# jackdemo.net
KiCad netlist of a schematic drawn in EAGLE
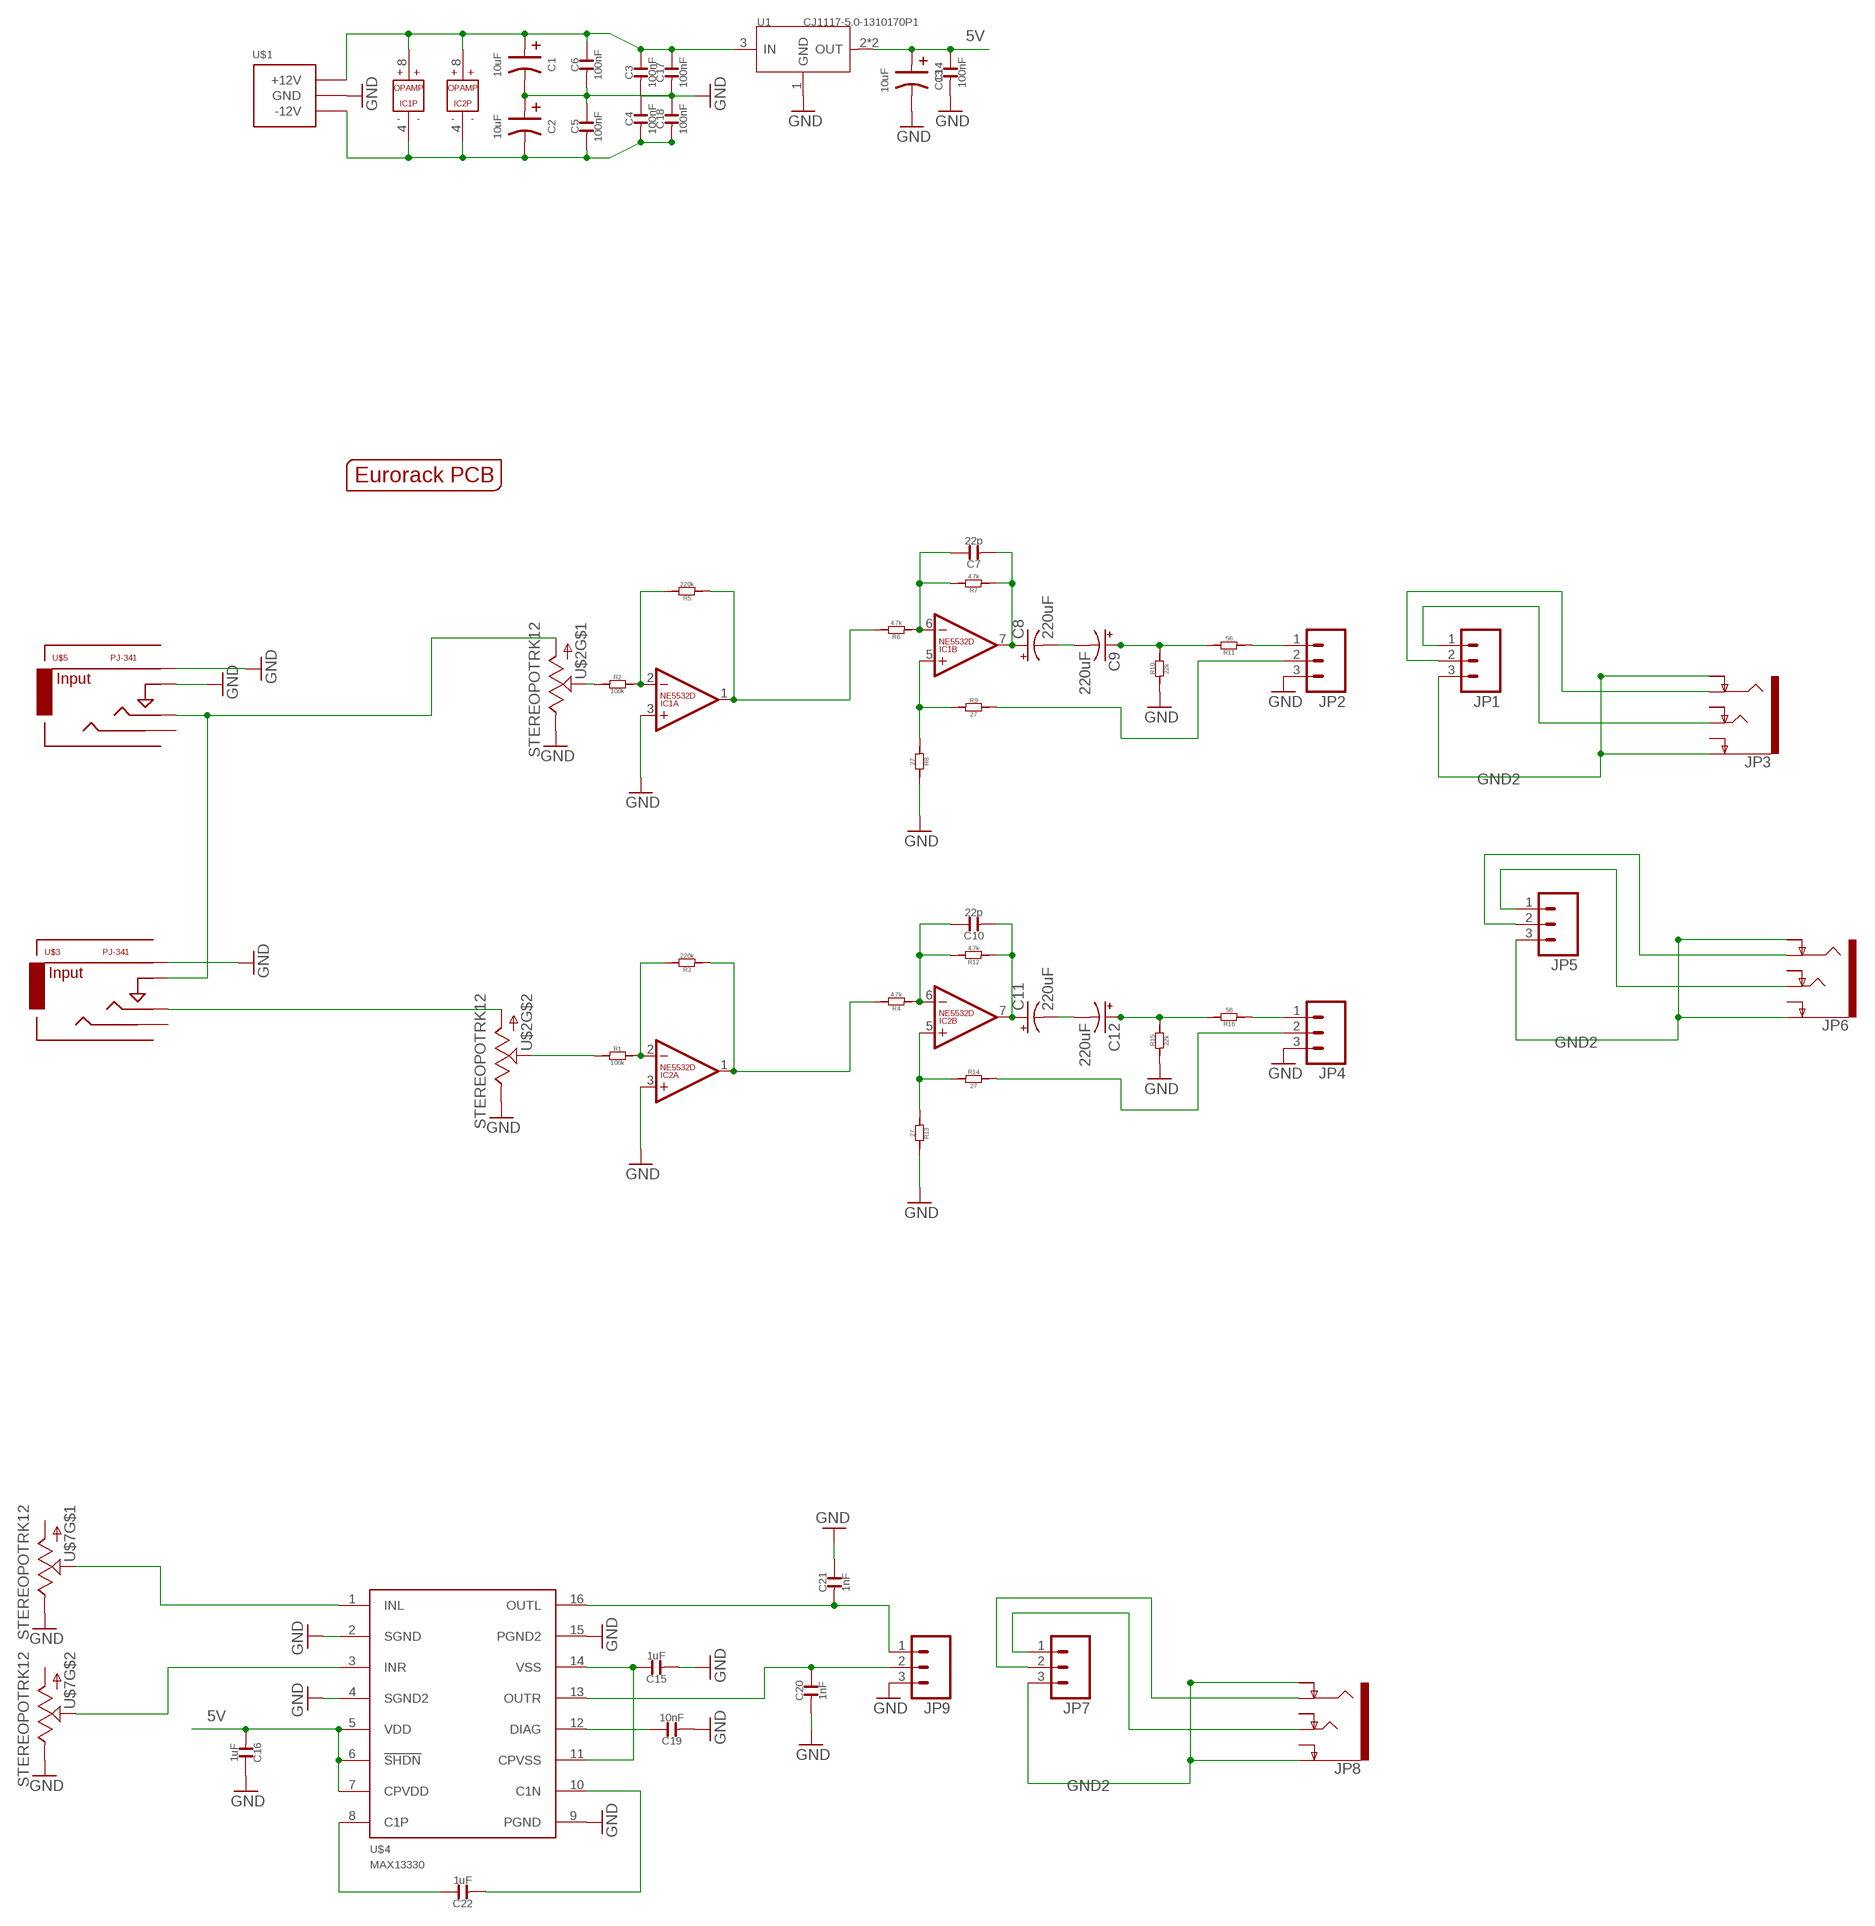
[diagram p0: schematic, sheet 1]

(export (version "E")
  (design (tool "Eeschema 10.0.6"))
  (components
    (comp (ref "C1")
      (value "10uF")
      (footprint "eagle-import:AVX-A")
      (libsource (lib "eagle-import") (part "C-POLAR-A"))
    )
    (comp (ref "C2")
      (value "10uF")
      (footprint "eagle-import:AVX-A")
      (libsource (lib "eagle-import") (part "C-POLAR-A"))
    )
    (comp (ref "C3")
      (value "100nF")
      (footprint "eagle-import:C0603")
      (libsource (lib "eagle-import") (part "C-0603"))
    )
    (comp (ref "C4")
      (value "100nF")
      (footprint "eagle-import:C0603")
      (libsource (lib "eagle-import") (part "C-0603"))
    )
    (comp (ref "C5")
      (value "100nF")
      (footprint "eagle-import:C0603")
      (libsource (lib "eagle-import") (part "C-0603"))
    )
    (comp (ref "C6")
      (value "100nF")
      (footprint "eagle-import:C0603")
      (libsource (lib "eagle-import") (part "C-0603"))
    )
    (comp (ref "C7")
      (value "22p")
      (footprint "eagle-import:C0603")
      (libsource (lib "eagle-import") (part "C-0603"))
    )
    (comp (ref "C8")
      (value "220uF")
      (footprint "eagle-import:153CLV-0505")
      (libsource (lib "eagle-import") (part "CPOL-US153CLV-0505"))
    )
    (comp (ref "C9")
      (value "220uF")
      (footprint "eagle-import:153CLV-0505")
      (libsource (lib "eagle-import") (part "CPOL-US153CLV-0505"))
    )
    (comp (ref "C10")
      (value "22p")
      (footprint "eagle-import:C0603")
      (libsource (lib "eagle-import") (part "C-0603"))
    )
    (comp (ref "C11")
      (value "220uF")
      (footprint "eagle-import:153CLV-0505")
      (libsource (lib "eagle-import") (part "CPOL-US153CLV-0505"))
    )
    (comp (ref "C12")
      (value "220uF")
      (footprint "eagle-import:153CLV-0505")
      (libsource (lib "eagle-import") (part "CPOL-US153CLV-0505"))
    )
    (comp (ref "C13")
      (value "10uF")
      (footprint "eagle-import:AVX-A")
      (libsource (lib "eagle-import") (part "C-POLAR-A"))
    )
    (comp (ref "C14")
      (value "100nF")
      (footprint "eagle-import:C0603")
      (libsource (lib "eagle-import") (part "C-0603"))
    )
    (comp (ref "C15")
      (value "1uF")
      (footprint "eagle-import:C0603")
      (libsource (lib "eagle-import") (part "C-0603"))
    )
    (comp (ref "C16")
      (value "1uF")
      (footprint "eagle-import:C0603")
      (libsource (lib "eagle-import") (part "C-0603"))
    )
    (comp (ref "C17")
      (value "100nF")
      (footprint "eagle-import:C0603")
      (libsource (lib "eagle-import") (part "C-0603"))
    )
    (comp (ref "C18")
      (value "100nF")
      (footprint "eagle-import:C0603")
      (libsource (lib "eagle-import") (part "C-0603"))
    )
    (comp (ref "C19")
      (value "10nF")
      (footprint "eagle-import:C0603")
      (libsource (lib "eagle-import") (part "C-0603"))
    )
    (comp (ref "C20")
      (value "1nF")
      (footprint "eagle-import:C0603")
      (libsource (lib "eagle-import") (part "C-0603"))
    )
    (comp (ref "C21")
      (value "1nF")
      (footprint "eagle-import:C0603")
      (libsource (lib "eagle-import") (part "C-0603"))
    )
    (comp (ref "C22")
      (value "1uF")
      (footprint "eagle-import:C0603")
      (libsource (lib "eagle-import") (part "C-0603"))
    )
    (comp (ref "IC1")
      (value "NE5532D")
      (footprint "eagle-import:SO08")
      (libsource (lib "eagle-import") (part "NE5532D"))
    )
    (comp (ref "IC2")
      (value "NE5532D")
      (footprint "eagle-import:SO08")
      (libsource (lib "eagle-import") (part "NE5532D"))
    )
    (comp (ref "JP1")
      (value "M03PTH")
      (footprint "eagle-import:1X03")
      (libsource (lib "eagle-import") (part "M03PTH"))
    )
    (comp (ref "JP2")
      (value "M03PTH")
      (footprint "eagle-import:1X03")
      (libsource (lib "eagle-import") (part "M03PTH"))
    )
    (comp (ref "JP3")
      (value "AUDIO-JACK4-.25-HORIZ-TRS")
      (footprint "eagle-import:AUDIO-JACK-.25-INCH-HORIZ-PTH")
      (libsource (lib "eagle-import") (part "AUDIO-JACK4-.25-HORIZ-TRS"))
    )
    (comp (ref "JP4")
      (value "M03PTH")
      (footprint "eagle-import:1X03")
      (libsource (lib "eagle-import") (part "M03PTH"))
    )
    (comp (ref "JP5")
      (value "M03PTH")
      (footprint "eagle-import:1X03")
      (libsource (lib "eagle-import") (part "M03PTH"))
    )
    (comp (ref "JP6")
      (value "AUDIO-JACK4-.25-HORIZ-TRS")
      (footprint "eagle-import:AUDIO-JACK-.25-INCH-HORIZ-PTH")
      (libsource (lib "eagle-import") (part "AUDIO-JACK4-.25-HORIZ-TRS"))
    )
    (comp (ref "JP7")
      (value "M03PTH")
      (footprint "eagle-import:1X03")
      (libsource (lib "eagle-import") (part "M03PTH"))
    )
    (comp (ref "JP8")
      (value "AUDIO-JACK4-.25-HORIZ-TRS")
      (footprint "eagle-import:AUDIO-JACK-.25-INCH-HORIZ-PTH")
      (libsource (lib "eagle-import") (part "AUDIO-JACK4-.25-HORIZ-TRS"))
    )
    (comp (ref "JP9")
      (value "M03PTH")
      (footprint "eagle-import:1X03")
      (libsource (lib "eagle-import") (part "M03PTH"))
    )
    (comp (ref "R1")
      (value "100k")
      (footprint "eagle-import:R0603")
      (libsource (lib "eagle-import") (part "R-0603"))
    )
    (comp (ref "R2")
      (value "100k")
      (footprint "eagle-import:R0603")
      (libsource (lib "eagle-import") (part "R-0603"))
    )
    (comp (ref "R3")
      (value "220k")
      (footprint "eagle-import:R0603")
      (libsource (lib "eagle-import") (part "R-0603"))
    )
    (comp (ref "R4")
      (value "4.7k")
      (footprint "eagle-import:R0603")
      (libsource (lib "eagle-import") (part "R-0603"))
    )
    (comp (ref "R5")
      (value "220k")
      (footprint "eagle-import:R0603")
      (libsource (lib "eagle-import") (part "R-0603"))
    )
    (comp (ref "R6")
      (value "4.7k")
      (footprint "eagle-import:R0603")
      (libsource (lib "eagle-import") (part "R-0603"))
    )
    (comp (ref "R7")
      (value "4.7k")
      (footprint "eagle-import:R0603")
      (libsource (lib "eagle-import") (part "R-0603"))
    )
    (comp (ref "R8")
      (value "27")
      (footprint "eagle-import:R0603")
      (libsource (lib "eagle-import") (part "R-0603"))
    )
    (comp (ref "R9")
      (value "27")
      (footprint "eagle-import:R0603")
      (libsource (lib "eagle-import") (part "R-0603"))
    )
    (comp (ref "R10")
      (value "22k")
      (footprint "eagle-import:R0603")
      (libsource (lib "eagle-import") (part "R-0603"))
    )
    (comp (ref "R11")
      (value "56")
      (footprint "eagle-import:R0603")
      (libsource (lib "eagle-import") (part "R-0603"))
    )
    (comp (ref "R12")
      (value "4.7k")
      (footprint "eagle-import:R0603")
      (libsource (lib "eagle-import") (part "R-0603"))
    )
    (comp (ref "R13")
      (value "27")
      (footprint "eagle-import:R0603")
      (libsource (lib "eagle-import") (part "R-0603"))
    )
    (comp (ref "R14")
      (value "27")
      (footprint "eagle-import:R0603")
      (libsource (lib "eagle-import") (part "R-0603"))
    )
    (comp (ref "R15")
      (value "22k")
      (footprint "eagle-import:R0603")
      (libsource (lib "eagle-import") (part "R-0603"))
    )
    (comp (ref "R16")
      (value "56")
      (footprint "eagle-import:R0603")
      (libsource (lib "eagle-import") (part "R-0603"))
    )
    (comp (ref "U$1")
      (value "POWER_SIMPLE")
      (footprint "eagle-import:2X05_SMT_HEADER")
      (libsource (lib "eagle-import") (part "POWER_SIMPLE"))
    )
    (comp (ref "U$2")
      (value "STEREOPOTRK12")
      (footprint "eagle-import:RK12")
      (libsource (lib "eagle-import") (part "STEREOPOTRK12"))
    )
    (comp (ref "U$3")
      (value "PJ-341")
      (footprint "eagle-import:3.5MM-JACK-SWITCH-13MM-INPUT")
      (libsource (lib "eagle-import") (part "AUDIO-JACKINPUT"))
    )
    (comp (ref "U$4")
      (value "MAX13330")
      (footprint "eagle-import:QSOP16")
      (libsource (lib "eagle-import") (part "MAX13330"))
    )
    (comp (ref "U$5")
      (value "PJ-341")
      (footprint "eagle-import:3.5MM-JACK-SWITCH-13MM-INPUT")
      (libsource (lib "eagle-import") (part "AUDIO-JACKINPUT"))
    )
    (comp (ref "U$6")
      (value "EURORACK_PCB4HP")
      (footprint "eagle-import:EURORACK4HPPCB")
      (libsource (lib "eagle-import") (part "EURORACK_PCB4HP"))
    )
    (comp (ref "U$7")
      (value "STEREOPOTRK12")
      (footprint "eagle-import:RK12")
      (libsource (lib "eagle-import") (part "STEREOPOTRK12"))
    )
    (comp (ref "U1")
      (value "CJ1117-5.0-1310170P1")
      (footprint "eagle-import:SOT223")
      (libsource (lib "eagle-import") (part "CJ1117-5.0-1310170P1"))
    )
  )
  (nets
    (net (code "1") (name "/5V") (class "Default")
      (node (ref "C13") (pin "+") (pinfunction "1_+") (pintype "bidirectional"))
      (node (ref "C14") (pin "2") (pinfunction "2_2") (pintype "bidirectional"))
      (node (ref "C16") (pin "1") (pinfunction "1_1") (pintype "bidirectional"))
      (node (ref "U$4") (pin "5") (pinfunction "VDD_5") (pintype "bidirectional"))
      (node (ref "U$4") (pin "6") (pinfunction "~{SHDN}_6") (pintype "bidirectional"))
      (node (ref "U$4") (pin "7") (pinfunction "CPVDD_7") (pintype "bidirectional"))
      (node (ref "U1") (pin "2") (pinfunction "OUT_2") (pintype "bidirectional"))
      (node (ref "U1") (pin "TER") (pinfunction "OUT_TER") (pintype "bidirectional"))
    )
    (net (code "2") (name "/GND2") (class "Default")
      (node (ref "JP1") (pin "3") (pinfunction "3_3") (pintype "passive"))
      (node (ref "JP3") (pin "P$2") (pinfunction "EARTH_P$2") (pintype "bidirectional"))
      (node (ref "JP3") (pin "P$5") (pinfunction "RING-NORM_P$5") (pintype "bidirectional"))
      (node (ref "JP5") (pin "3") (pinfunction "3_3") (pintype "passive"))
      (node (ref "JP6") (pin "P$2") (pinfunction "EARTH_P$2") (pintype "bidirectional"))
      (node (ref "JP6") (pin "P$5") (pinfunction "RING-NORM_P$5") (pintype "bidirectional"))
      (node (ref "JP7") (pin "3") (pinfunction "3_3") (pintype "passive"))
      (node (ref "JP8") (pin "P$2") (pinfunction "EARTH_P$2") (pintype "bidirectional"))
      (node (ref "JP8") (pin "P$5") (pinfunction "RING-NORM_P$5") (pintype "bidirectional"))
    )
    (net (code "3") (name "GND") (class "Default")
      (node (ref "C1") (pin "-") (pinfunction "2_-") (pintype "bidirectional"))
      (node (ref "C13") (pin "-") (pinfunction "2_-") (pintype "bidirectional"))
      (node (ref "C14") (pin "1") (pinfunction "1_1") (pintype "bidirectional"))
      (node (ref "C15") (pin "1") (pinfunction "1_1") (pintype "bidirectional"))
      (node (ref "C16") (pin "2") (pinfunction "2_2") (pintype "bidirectional"))
      (node (ref "C17") (pin "1") (pinfunction "1_1") (pintype "bidirectional"))
      (node (ref "C18") (pin "2") (pinfunction "2_2") (pintype "bidirectional"))
      (node (ref "C19") (pin "1") (pinfunction "1_1") (pintype "bidirectional"))
      (node (ref "C2") (pin "+") (pinfunction "1_+") (pintype "bidirectional"))
      (node (ref "C20") (pin "1") (pinfunction "1_1") (pintype "bidirectional"))
      (node (ref "C21") (pin "2") (pinfunction "2_2") (pintype "bidirectional"))
      (node (ref "C3") (pin "1") (pinfunction "1_1") (pintype "bidirectional"))
      (node (ref "C4") (pin "2") (pinfunction "2_2") (pintype "bidirectional"))
      (node (ref "C5") (pin "2") (pinfunction "2_2") (pintype "bidirectional"))
      (node (ref "C6") (pin "1") (pinfunction "1_1") (pintype "bidirectional"))
      (node (ref "IC1") (pin "3") (pinfunction "+IN_3") (pintype "input"))
      (node (ref "IC2") (pin "3") (pinfunction "+IN_3") (pintype "input"))
      (node (ref "JP2") (pin "3") (pinfunction "3_3") (pintype "passive"))
      (node (ref "JP4") (pin "3") (pinfunction "3_3") (pintype "passive"))
      (node (ref "JP9") (pin "3") (pinfunction "3_3") (pintype "passive"))
      (node (ref "R10") (pin "1") (pinfunction "1_1") (pintype "bidirectional"))
      (node (ref "R13") (pin "2") (pinfunction "2_2") (pintype "bidirectional"))
      (node (ref "R15") (pin "1") (pinfunction "1_1") (pintype "bidirectional"))
      (node (ref "R8") (pin "2") (pinfunction "2_2") (pintype "bidirectional"))
      (node (ref "U$1") (pin "3") (pinfunction "GND_3") (pintype "bidirectional"))
      (node (ref "U$1") (pin "4") (pinfunction "GND_4") (pintype "bidirectional"))
      (node (ref "U$1") (pin "5") (pinfunction "GND_5") (pintype "bidirectional"))
      (node (ref "U$1") (pin "6") (pinfunction "GND_6") (pintype "bidirectional"))
      (node (ref "U$1") (pin "7") (pinfunction "GND_7") (pintype "bidirectional"))
      (node (ref "U$1") (pin "8") (pinfunction "GND_8") (pintype "bidirectional"))
      (node (ref "U$2") (pin "R1_1") (pinfunction "E_R1_1") (pintype "passive"))
      (node (ref "U$2") (pin "R2_1") (pinfunction "E_R2_1") (pintype "passive"))
      (node (ref "U$3") (pin "RING@3") (pinfunction "RING_RING@3") (pintype "bidirectional"))
      (node (ref "U$4") (pin "15") (pinfunction "PGND2_15") (pintype "bidirectional"))
      (node (ref "U$4") (pin "2") (pinfunction "SGND_2") (pintype "bidirectional"))
      (node (ref "U$4") (pin "4") (pinfunction "SGND2_4") (pintype "bidirectional"))
      (node (ref "U$4") (pin "9") (pinfunction "PGND_9") (pintype "bidirectional"))
      (node (ref "U$5") (pin "RING@3") (pinfunction "RING_RING@3") (pintype "bidirectional"))
      (node (ref "U$5") (pin "SWITCH@3") (pinfunction "SWITCH_SWITCH@3") (pintype "bidirectional"))
      (node (ref "U$7") (pin "R1_1") (pinfunction "E_R1_1") (pintype "passive"))
      (node (ref "U$7") (pin "R2_1") (pinfunction "E_R2_1") (pintype "passive"))
      (node (ref "U1") (pin "1") (pinfunction "GND_1") (pintype "bidirectional"))
    )
    (net (code "4") (name "Net-(C1-1)") (class "Default")
      (node (ref "C1") (pin "+") (pinfunction "1_+") (pintype "bidirectional"))
      (node (ref "C17") (pin "2") (pinfunction "2_2") (pintype "bidirectional"))
      (node (ref "C3") (pin "2") (pinfunction "2_2") (pintype "bidirectional"))
      (node (ref "C6") (pin "2") (pinfunction "2_2") (pintype "bidirectional"))
      (node (ref "IC1") (pin "8") (pinfunction "V+_8") (pintype "power_in"))
      (node (ref "IC2") (pin "8") (pinfunction "V+_8") (pintype "power_in"))
      (node (ref "U$1") (pin "10") (pinfunction "+12V_10") (pintype "bidirectional"))
      (node (ref "U$1") (pin "9") (pinfunction "+12V_9") (pintype "bidirectional"))
      (node (ref "U1") (pin "3") (pinfunction "IN_3") (pintype "bidirectional"))
    )
    (net (code "5") (name "Net-(C2-2)") (class "Default")
      (node (ref "C18") (pin "1") (pinfunction "1_1") (pintype "bidirectional"))
      (node (ref "C2") (pin "-") (pinfunction "2_-") (pintype "bidirectional"))
      (node (ref "C4") (pin "1") (pinfunction "1_1") (pintype "bidirectional"))
      (node (ref "C5") (pin "1") (pinfunction "1_1") (pintype "bidirectional"))
      (node (ref "IC1") (pin "4") (pinfunction "V-_4") (pintype "power_in"))
      (node (ref "IC2") (pin "4") (pinfunction "V-_4") (pintype "power_in"))
      (node (ref "U$1") (pin "1") (pinfunction "-12V_1") (pintype "bidirectional"))
      (node (ref "U$1") (pin "2") (pinfunction "-12V_2") (pintype "bidirectional"))
    )
    (net (code "6") (name "Net-(C8-Pad-)") (class "Default")
      (node (ref "C8") (pin "-") (pinfunction "-_-") (pintype "passive"))
      (node (ref "C9") (pin "-") (pinfunction "-_-") (pintype "passive"))
    )
    (net (code "7") (name "Net-(C9-Pad+)") (class "Default")
      (node (ref "C9") (pin "+") (pinfunction "+_+") (pintype "passive"))
      (node (ref "R10") (pin "2") (pinfunction "2_2") (pintype "bidirectional"))
      (node (ref "R11") (pin "2") (pinfunction "2_2") (pintype "bidirectional"))
    )
    (net (code "8") (name "Net-(C11-Pad-)") (class "Default")
      (node (ref "C11") (pin "-") (pinfunction "-_-") (pintype "passive"))
      (node (ref "C12") (pin "-") (pinfunction "-_-") (pintype "passive"))
    )
    (net (code "9") (name "Net-(C12-Pad+)") (class "Default")
      (node (ref "C12") (pin "+") (pinfunction "+_+") (pintype "passive"))
      (node (ref "R15") (pin "2") (pinfunction "2_2") (pintype "bidirectional"))
      (node (ref "R16") (pin "2") (pinfunction "2_2") (pintype "bidirectional"))
    )
    (net (code "10") (name "Net-(IC1A--IN)") (class "Default")
      (node (ref "IC1") (pin "2") (pinfunction "-IN_2") (pintype "input"))
      (node (ref "R2") (pin "2") (pinfunction "2_2") (pintype "bidirectional"))
      (node (ref "R5") (pin "2") (pinfunction "2_2") (pintype "bidirectional"))
    )
    (net (code "11") (name "Net-(IC1A-OUT)") (class "Default")
      (node (ref "IC1") (pin "1") (pinfunction "OUT_1") (pintype "output"))
      (node (ref "R5") (pin "1") (pinfunction "1_1") (pintype "bidirectional"))
      (node (ref "R6") (pin "2") (pinfunction "2_2") (pintype "bidirectional"))
    )
    (net (code "12") (name "Net-(IC1B-+IN)") (class "Default")
      (node (ref "IC1") (pin "5") (pinfunction "+IN_5") (pintype "input"))
      (node (ref "R8") (pin "1") (pinfunction "1_1") (pintype "bidirectional"))
      (node (ref "R9") (pin "1") (pinfunction "1_1") (pintype "bidirectional"))
    )
    (net (code "13") (name "Net-(IC1B--IN)") (class "Default")
      (node (ref "C7") (pin "2") (pinfunction "2_2") (pintype "bidirectional"))
      (node (ref "IC1") (pin "6") (pinfunction "-IN_6") (pintype "input"))
      (node (ref "R6") (pin "1") (pinfunction "1_1") (pintype "bidirectional"))
      (node (ref "R7") (pin "2") (pinfunction "2_2") (pintype "bidirectional"))
    )
    (net (code "14") (name "Net-(IC1B-OUT)") (class "Default")
      (node (ref "C7") (pin "1") (pinfunction "1_1") (pintype "bidirectional"))
      (node (ref "C8") (pin "+") (pinfunction "+_+") (pintype "passive"))
      (node (ref "IC1") (pin "7") (pinfunction "OUT_7") (pintype "output"))
      (node (ref "R7") (pin "1") (pinfunction "1_1") (pintype "bidirectional"))
    )
    (net (code "15") (name "Net-(IC2A--IN)") (class "Default")
      (node (ref "IC2") (pin "2") (pinfunction "-IN_2") (pintype "input"))
      (node (ref "R1") (pin "2") (pinfunction "2_2") (pintype "bidirectional"))
      (node (ref "R3") (pin "2") (pinfunction "2_2") (pintype "bidirectional"))
    )
    (net (code "16") (name "Net-(IC2A-OUT)") (class "Default")
      (node (ref "IC2") (pin "1") (pinfunction "OUT_1") (pintype "output"))
      (node (ref "R3") (pin "1") (pinfunction "1_1") (pintype "bidirectional"))
      (node (ref "R4") (pin "2") (pinfunction "2_2") (pintype "bidirectional"))
    )
    (net (code "17") (name "Net-(IC2B-+IN)") (class "Default")
      (node (ref "IC2") (pin "5") (pinfunction "+IN_5") (pintype "input"))
      (node (ref "R13") (pin "1") (pinfunction "1_1") (pintype "bidirectional"))
      (node (ref "R14") (pin "1") (pinfunction "1_1") (pintype "bidirectional"))
    )
    (net (code "18") (name "Net-(IC2B--IN)") (class "Default")
      (node (ref "C10") (pin "2") (pinfunction "2_2") (pintype "bidirectional"))
      (node (ref "IC2") (pin "6") (pinfunction "-IN_6") (pintype "input"))
      (node (ref "R12") (pin "2") (pinfunction "2_2") (pintype "bidirectional"))
      (node (ref "R4") (pin "1") (pinfunction "1_1") (pintype "bidirectional"))
    )
    (net (code "19") (name "Net-(IC2B-OUT)") (class "Default")
      (node (ref "C10") (pin "1") (pinfunction "1_1") (pintype "bidirectional"))
      (node (ref "C11") (pin "+") (pinfunction "+_+") (pintype "passive"))
      (node (ref "IC2") (pin "7") (pinfunction "OUT_7") (pintype "output"))
      (node (ref "R12") (pin "1") (pinfunction "1_1") (pintype "bidirectional"))
    )
    (net (code "20") (name "Net-(JP2-Pad1)") (class "Default")
      (node (ref "JP2") (pin "1") (pinfunction "1_1") (pintype "passive"))
      (node (ref "R11") (pin "1") (pinfunction "1_1") (pintype "bidirectional"))
    )
    (net (code "21") (name "Net-(JP2-Pad2)") (class "Default")
      (node (ref "JP2") (pin "2") (pinfunction "2_2") (pintype "passive"))
      (node (ref "R9") (pin "2") (pinfunction "2_2") (pintype "bidirectional"))
    )
    (net (code "22") (name "Net-(JP3-RING)") (class "Default")
      (node (ref "JP1") (pin "2") (pinfunction "2_2") (pintype "passive"))
      (node (ref "JP3") (pin "P$4") (pinfunction "RING_P$4") (pintype "bidirectional"))
    )
    (net (code "23") (name "Net-(JP3-TIP)") (class "Default")
      (node (ref "JP1") (pin "1") (pinfunction "1_1") (pintype "passive"))
      (node (ref "JP3") (pin "P$6") (pinfunction "TIP_P$6") (pintype "bidirectional"))
    )
    (net (code "24") (name "Net-(JP4-Pad1)") (class "Default")
      (node (ref "JP4") (pin "1") (pinfunction "1_1") (pintype "passive"))
      (node (ref "R16") (pin "1") (pinfunction "1_1") (pintype "bidirectional"))
    )
    (net (code "25") (name "Net-(JP4-Pad2)") (class "Default")
      (node (ref "JP4") (pin "2") (pinfunction "2_2") (pintype "passive"))
      (node (ref "R14") (pin "2") (pinfunction "2_2") (pintype "bidirectional"))
    )
    (net (code "26") (name "Net-(JP6-RING)") (class "Default")
      (node (ref "JP5") (pin "2") (pinfunction "2_2") (pintype "passive"))
      (node (ref "JP6") (pin "P$4") (pinfunction "RING_P$4") (pintype "bidirectional"))
    )
    (net (code "27") (name "Net-(JP6-TIP)") (class "Default")
      (node (ref "JP5") (pin "1") (pinfunction "1_1") (pintype "passive"))
      (node (ref "JP6") (pin "P$6") (pinfunction "TIP_P$6") (pintype "bidirectional"))
    )
    (net (code "28") (name "Net-(JP8-RING)") (class "Default")
      (node (ref "JP7") (pin "2") (pinfunction "2_2") (pintype "passive"))
      (node (ref "JP8") (pin "P$4") (pinfunction "RING_P$4") (pintype "bidirectional"))
    )
    (net (code "29") (name "Net-(JP8-TIP)") (class "Default")
      (node (ref "JP7") (pin "1") (pinfunction "1_1") (pintype "passive"))
      (node (ref "JP8") (pin "P$6") (pinfunction "TIP_P$6") (pintype "bidirectional"))
    )
    (net (code "30") (name "Net-(U$2A-A)") (class "Default")
      (node (ref "U$2") (pin "R1_3") (pinfunction "A_R1_3") (pintype "passive"))
      (node (ref "U$3") (pin "SWITCH@3") (pinfunction "SWITCH_SWITCH@3") (pintype "bidirectional"))
      (node (ref "U$5") (pin "TIP@3") (pinfunction "TIP_TIP@3") (pintype "bidirectional"))
    )
    (net (code "31") (name "Net-(U$2A-S)") (class "Default")
      (node (ref "R2") (pin "1") (pinfunction "1_1") (pintype "bidirectional"))
      (node (ref "U$2") (pin "R1_2") (pinfunction "S_R1_2") (pintype "passive"))
    )
    (net (code "32") (name "Net-(U$2B-A)") (class "Default")
      (node (ref "U$2") (pin "R2_3") (pinfunction "A_R2_3") (pintype "passive"))
      (node (ref "U$3") (pin "TIP@3") (pinfunction "TIP_TIP@3") (pintype "bidirectional"))
    )
    (net (code "33") (name "Net-(U$2B-S)") (class "Default")
      (node (ref "R1") (pin "1") (pinfunction "1_1") (pintype "bidirectional"))
      (node (ref "U$2") (pin "R2_2") (pinfunction "S_R2_2") (pintype "passive"))
    )
    (net (code "34") (name "Net-(U$4-C1N)") (class "Default")
      (node (ref "C22") (pin "1") (pinfunction "1_1") (pintype "bidirectional"))
      (node (ref "U$4") (pin "10") (pinfunction "C1N_10") (pintype "bidirectional"))
    )
    (net (code "35") (name "Net-(U$4-C1P)") (class "Default")
      (node (ref "C22") (pin "2") (pinfunction "2_2") (pintype "bidirectional"))
      (node (ref "U$4") (pin "8") (pinfunction "C1P_8") (pintype "bidirectional"))
    )
    (net (code "36") (name "Net-(U$4-CPVSS)") (class "Default")
      (node (ref "C15") (pin "2") (pinfunction "2_2") (pintype "bidirectional"))
      (node (ref "U$4") (pin "11") (pinfunction "CPVSS_11") (pintype "bidirectional"))
      (node (ref "U$4") (pin "14") (pinfunction "VSS_14") (pintype "bidirectional"))
    )
    (net (code "37") (name "Net-(U$4-DIAG)") (class "Default")
      (node (ref "C19") (pin "2") (pinfunction "2_2") (pintype "bidirectional"))
      (node (ref "U$4") (pin "12") (pinfunction "DIAG_12") (pintype "bidirectional"))
    )
    (net (code "38") (name "Net-(U$4-INL)") (class "Default")
      (node (ref "U$4") (pin "1") (pinfunction "INL_1") (pintype "bidirectional"))
      (node (ref "U$7") (pin "R1_2") (pinfunction "S_R1_2") (pintype "passive"))
    )
    (net (code "39") (name "Net-(U$4-INR)") (class "Default")
      (node (ref "U$4") (pin "3") (pinfunction "INR_3") (pintype "bidirectional"))
      (node (ref "U$7") (pin "R2_2") (pinfunction "S_R2_2") (pintype "passive"))
    )
    (net (code "40") (name "Net-(U$4-OUTL)") (class "Default")
      (node (ref "C21") (pin "1") (pinfunction "1_1") (pintype "bidirectional"))
      (node (ref "JP9") (pin "1") (pinfunction "1_1") (pintype "passive"))
      (node (ref "U$4") (pin "16") (pinfunction "OUTL_16") (pintype "bidirectional"))
    )
    (net (code "41") (name "Net-(U$4-OUTR)") (class "Default")
      (node (ref "C20") (pin "2") (pinfunction "2_2") (pintype "bidirectional"))
      (node (ref "JP9") (pin "2") (pinfunction "2_2") (pintype "passive"))
      (node (ref "U$4") (pin "13") (pinfunction "OUTR_13") (pintype "bidirectional"))
    )
    (net (code "42") (name "unconnected-(JP3-EARTH-NORM-PadP$3)") (class "Default")
      (node (ref "JP3") (pin "P$3") (pinfunction "EARTH-NORM_P$3") (pintype "bidirectional"))
    )
    (net (code "43") (name "unconnected-(JP3-TIP-NORM-PadP$7)") (class "Default")
      (node (ref "JP3") (pin "P$7") (pinfunction "TIP-NORM_P$7") (pintype "bidirectional"))
    )
    (net (code "44") (name "unconnected-(JP6-EARTH-NORM-PadP$3)") (class "Default")
      (node (ref "JP6") (pin "P$3") (pinfunction "EARTH-NORM_P$3") (pintype "bidirectional"))
    )
    (net (code "45") (name "unconnected-(JP6-TIP-NORM-PadP$7)") (class "Default")
      (node (ref "JP6") (pin "P$7") (pinfunction "TIP-NORM_P$7") (pintype "bidirectional"))
    )
    (net (code "46") (name "unconnected-(JP8-EARTH-NORM-PadP$3)") (class "Default")
      (node (ref "JP8") (pin "P$3") (pinfunction "EARTH-NORM_P$3") (pintype "bidirectional"))
    )
    (net (code "47") (name "unconnected-(JP8-TIP-NORM-PadP$7)") (class "Default")
      (node (ref "JP8") (pin "P$7") (pinfunction "TIP-NORM_P$7") (pintype "bidirectional"))
    )
    (net (code "48") (name "unconnected-(U$3-SECOND-PadSECOND@3)") (class "Default")
      (node (ref "U$3") (pin "SECOND@3") (pinfunction "SECOND_SECOND@3") (pintype "bidirectional"))
    )
    (net (code "49") (name "unconnected-(U$5-SECOND-PadSECOND@3)") (class "Default")
      (node (ref "U$5") (pin "SECOND@3") (pinfunction "SECOND_SECOND@3") (pintype "bidirectional"))
    )
    (net (code "50") (name "unconnected-(U$7A-A-PadR1_3)") (class "Default")
      (node (ref "U$7") (pin "R1_3") (pinfunction "A_R1_3") (pintype "passive"))
    )
    (net (code "51") (name "unconnected-(U$7B-A-PadR2_3)") (class "Default")
      (node (ref "U$7") (pin "R2_3") (pinfunction "A_R2_3") (pintype "passive"))
    )
  )
)
